# Lab2.net
KiCad netlist of a schematic drawn in Altium Designer
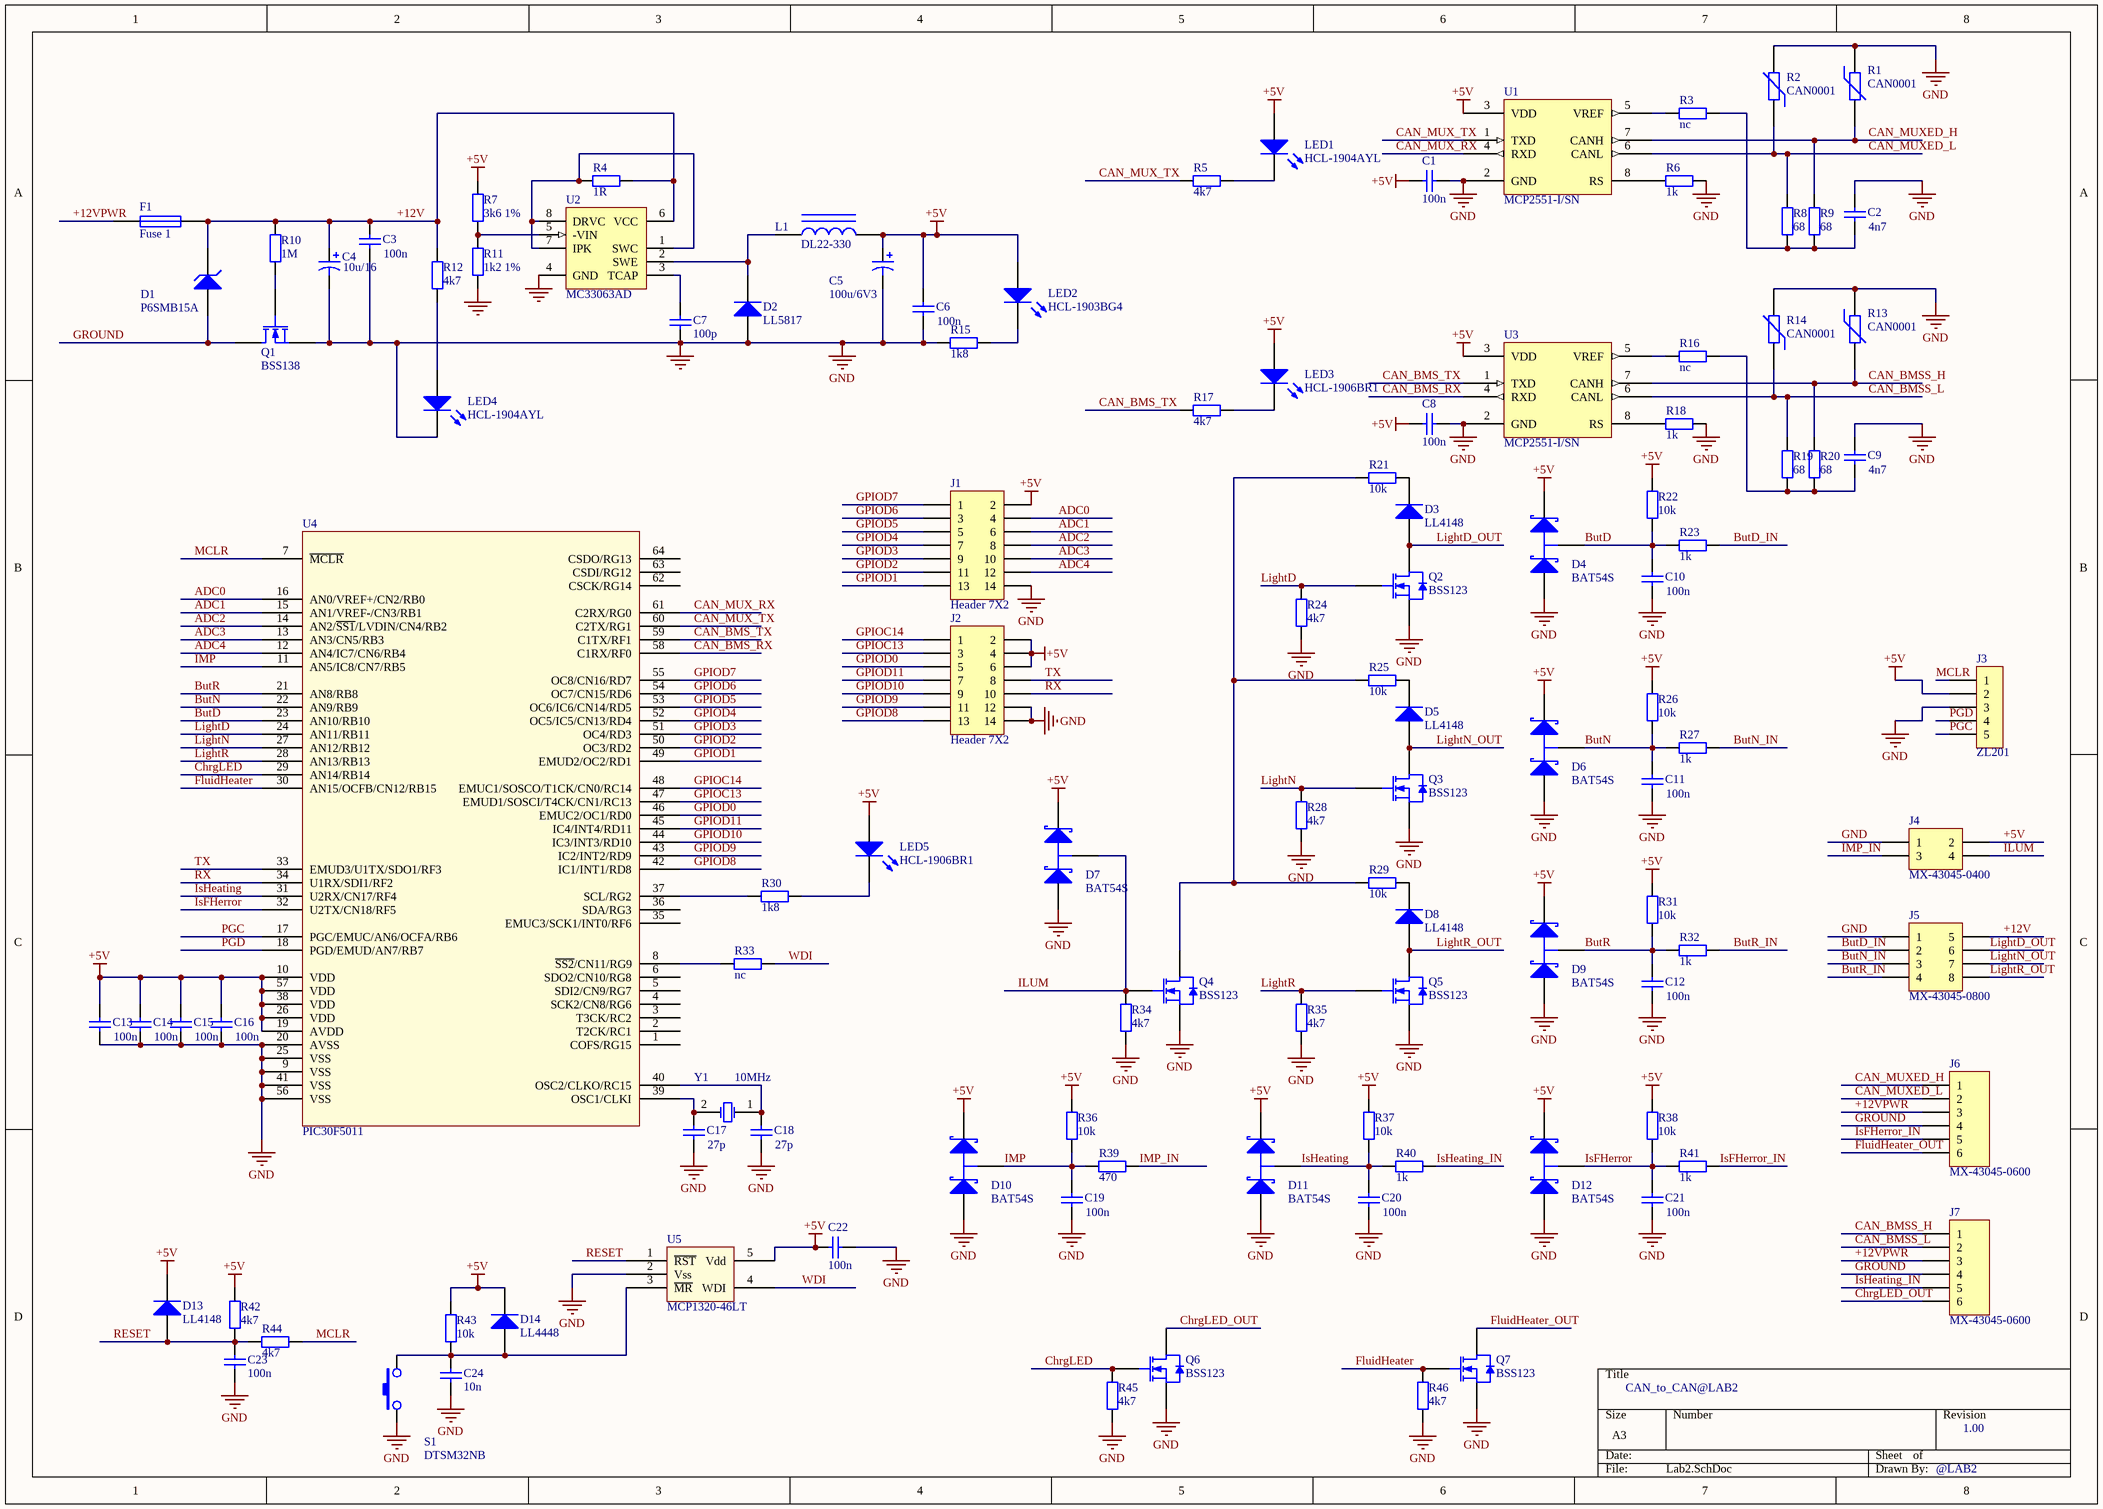
[diagram p0: Lab2.SchDoc]

(export (version "E")
  (design (tool "Eeschema 10.0.6"))
  (components
    (comp (ref "C1")
      (value "100n")
      (footprint "0603")
      (description "Capacitor")
      (libsource (lib "Miscellaneous Devices") (part "Cap"))
    )
    (comp (ref "C2")
      (value "4n7")
      (footprint "0603")
      (description "Capacitor")
      (libsource (lib "Miscellaneous Devices") (part "Cap"))
    )
    (comp (ref "C3")
      (value "100n")
      (footprint "3.5X2.8X1.9")
      (description "Capacitor")
      (libsource (lib "Miscellaneous Devices") (part "Cap"))
    )
    (comp (ref "C4")
      (value "10u/16")
      (footprint "3.5X2.8X1.9")
      (description "Polarized Capacitor (Radial)")
      (libsource (lib "Miscellaneous Devices") (part "Cap Pol1"))
    )
    (comp (ref "C5")
      (value "100u/6V3")
      (footprint "3.5X2.8X1.9")
      (description "Polarized Capacitor (Radial)")
      (libsource (lib "Miscellaneous Devices") (part "Cap Pol1"))
    )
    (comp (ref "C6")
      (value "100n")
      (footprint "0603")
      (description "Capacitor")
      (libsource (lib "Miscellaneous Devices") (part "Cap"))
    )
    (comp (ref "C7")
      (value "100p")
      (footprint "0603")
      (description "Capacitor")
      (libsource (lib "Miscellaneous Devices") (part "Cap"))
    )
    (comp (ref "C8")
      (value "100n")
      (footprint "0603")
      (description "Capacitor")
      (libsource (lib "Miscellaneous Devices") (part "Cap"))
    )
    (comp (ref "C9")
      (value "4n7")
      (footprint "0603")
      (description "Capacitor")
      (libsource (lib "Miscellaneous Devices") (part "Cap"))
    )
    (comp (ref "C10")
      (value "100n")
      (footprint "0603")
      (description "Capacitor")
      (libsource (lib "Miscellaneous Devices") (part "Cap"))
    )
    (comp (ref "C11")
      (value "100n")
      (footprint "0603")
      (description "Capacitor")
      (libsource (lib "Miscellaneous Devices") (part "Cap"))
    )
    (comp (ref "C12")
      (value "100n")
      (footprint "0603")
      (description "Capacitor")
      (libsource (lib "Miscellaneous Devices") (part "Cap"))
    )
    (comp (ref "C13")
      (value "100n")
      (footprint "0603")
      (description "Capacitor")
      (libsource (lib "Miscellaneous Devices") (part "Cap"))
    )
    (comp (ref "C14")
      (value "100n")
      (footprint "0603")
      (description "Capacitor")
      (libsource (lib "Miscellaneous Devices") (part "Cap"))
    )
    (comp (ref "C15")
      (value "100n")
      (footprint "0603")
      (description "Capacitor")
      (libsource (lib "Miscellaneous Devices") (part "Cap"))
    )
    (comp (ref "C16")
      (value "100n")
      (footprint "0603")
      (description "Capacitor")
      (libsource (lib "Miscellaneous Devices") (part "Cap"))
    )
    (comp (ref "C17")
      (value "27p")
      (footprint "0603")
      (description "Capacitor")
      (libsource (lib "Miscellaneous Devices") (part "Cap"))
    )
    (comp (ref "C18")
      (value "27p")
      (footprint "0603")
      (description "Capacitor")
      (libsource (lib "Miscellaneous Devices") (part "Cap"))
    )
    (comp (ref "C19")
      (value "100n")
      (footprint "0603")
      (description "Capacitor")
      (libsource (lib "Miscellaneous Devices") (part "Cap"))
    )
    (comp (ref "C20")
      (value "100n")
      (footprint "0603")
      (description "Capacitor")
      (libsource (lib "Miscellaneous Devices") (part "Cap"))
    )
    (comp (ref "C21")
      (value "100n")
      (footprint "0603")
      (description "Capacitor")
      (libsource (lib "Miscellaneous Devices") (part "Cap"))
    )
    (comp (ref "C22")
      (value "100n")
      (footprint "0603")
      (description "Capacitor")
      (libsource (lib "Miscellaneous Devices") (part "Cap"))
    )
    (comp (ref "C23")
      (value "100n")
      (footprint "0603")
      (description "Capacitor")
      (libsource (lib "Miscellaneous Devices") (part "Cap"))
    )
    (comp (ref "C24")
      (value "10n")
      (footprint "0603")
      (description "Capacitor")
      (libsource (lib "Miscellaneous Devices") (part "Cap"))
    )
    (comp (ref "D1")
      (value "P6SMB15A")
      (footprint "SMB")
      (description "Zener Diode")
      (libsource (lib "Miscellaneous Devices") (part "D Zener"))
    )
    (comp (ref "D2")
      (value "LL5817")
      (footprint "425")
      (description "High Conductance Fast Diode")
      (libsource (lib "FSC Discrete Diode") (part "1N4148"))
    )
    (comp (ref "D3")
      (value "LL4148")
      (footprint "6-0805_L")
      (description "High Conductance Fast Diode")
      (libsource (lib "FSC Discrete Diode") (part "1N4148"))
    )
    (comp (ref "D4")
      (value "BAT54S")
      (footprint "6-0805_L")
      (description "Schottky Barrier Double Diode")
      (libsource (lib "Philips Discrete Diode - Schottky") (part "BAT54S"))
    )
    (comp (ref "D5")
      (value "LL4148")
      (footprint "6-0805_L")
      (description "High Conductance Fast Diode")
      (libsource (lib "FSC Discrete Diode") (part "1N4148"))
    )
    (comp (ref "D6")
      (value "BAT54S")
      (footprint "SOT23_M")
      (description "Schottky Barrier Double Diode")
      (libsource (lib "Philips Discrete Diode - Schottky") (part "BAT54S"))
    )
    (comp (ref "D7")
      (value "BAT54S")
      (footprint "SOT-23B_M")
      (description "Schottky Barrier Double Diode")
      (libsource (lib "Philips Discrete Diode - Schottky") (part "BAT54S"))
    )
    (comp (ref "D8")
      (value "LL4148")
      (footprint "6-0805_L")
      (description "High Conductance Fast Diode")
      (libsource (lib "FSC Discrete Diode") (part "1N4148"))
    )
    (comp (ref "D9")
      (value "BAT54S")
      (footprint "SOT23_M")
      (description "Schottky Barrier Double Diode")
      (libsource (lib "Philips Discrete Diode - Schottky") (part "BAT54S"))
    )
    (comp (ref "D10")
      (value "BAT54S")
      (footprint "SOT23_M")
      (description "Schottky Barrier Double Diode")
      (libsource (lib "Philips Discrete Diode - Schottky") (part "BAT54S"))
    )
    (comp (ref "D11")
      (value "BAT54S")
      (footprint "SOT23_M")
      (description "Schottky Barrier Double Diode")
      (libsource (lib "Philips Discrete Diode - Schottky") (part "BAT54S"))
    )
    (comp (ref "D12")
      (value "BAT54S")
      (footprint "SOT23_M")
      (description "Schottky Barrier Double Diode")
      (libsource (lib "Philips Discrete Diode - Schottky") (part "BAT54S"))
    )
    (comp (ref "D13")
      (value "LL4148")
      (footprint "3.2X1.6X1.1")
      (description "High Conductance Fast Diode")
      (libsource (lib "FSC Discrete Diode") (part "1N4148"))
    )
    (comp (ref "D14")
      (value "LL4448")
      (footprint "3.2X1.6X1.1")
      (description "Default Diode")
      (libsource (lib "Miscellaneous Devices") (part "Diode"))
    )
    (comp (ref "F1")
      (value "Fuse 1")
      (footprint "1812")
      (description "Fuse")
      (libsource (lib "Miscellaneous Devices") (part "Fuse 1"))
    )
    (comp (ref "J1")
      (value "Header 7X2")
      (footprint "HDR2X7")
      (description "Header, 7-Pin, Dual row")
      (libsource (lib "Miscellaneous Connectors") (part "Header 7X2"))
    )
    (comp (ref "J2")
      (value "Header 7X2")
      (footprint "HDR2X7")
      (description "Header, 7-Pin, Dual row")
      (libsource (lib "Miscellaneous Connectors") (part "Header 7X2"))
    )
    (comp (ref "J3")
      (value "ZL201")
      (footprint "HDR1X5")
      (description "Connector")
      (libsource (lib "*") (part "CON5"))
    )
    (comp (ref "J4")
      (value "MX-43045-0400")
      (footprint "HDR2X2")
      (description "Header, 2-Pin, Dual row")
      (libsource (lib "Miscellaneous Connectors") (part "Header 2X2"))
    )
    (comp (ref "J5")
      (value "MX-43045-0800")
      (footprint "HDR2X4")
      (description "Header, 4-Pin, Dual row")
      (libsource (lib "Miscellaneous Connectors") (part "Header 4X2A"))
    )
    (comp (ref "J6")
      (value "MX-43045-0600")
      (footprint "HDR2X3")
      (description "Header, 6-Pin")
      (libsource (lib "Miscellaneous Connectors") (part "Header 6"))
    )
    (comp (ref "J7")
      (value "MX-43045-0600")
      (footprint "HDR2X3")
      (description "Header, 6-Pin")
      (libsource (lib "Miscellaneous Connectors") (part "Header 6"))
    )
    (comp (ref "L1")
      (value "DL22-330")
      (footprint "AXIAL-0.4")
      (description "Magnetic-Core Inductor")
      (libsource (lib "Miscellaneous Devices") (part "Inductor Iron"))
    )
    (comp (ref "LED1")
      (value "HCL-1904AYL")
      (footprint "0603")
      (description "Typical BLUE SiC LED")
      (libsource (lib "Miscellaneous Devices") (part "LED3"))
    )
    (comp (ref "LED2")
      (value "HCL-1903BG4")
      (footprint "0603")
      (description "Typical BLUE SiC LED")
      (libsource (lib "Miscellaneous Devices") (part "LED3"))
    )
    (comp (ref "LED3")
      (value "HCL-1906BR1")
      (footprint "0603")
      (description "Typical BLUE SiC LED")
      (libsource (lib "Miscellaneous Devices") (part "LED3"))
    )
    (comp (ref "LED4")
      (value "HCL-1904AYL")
      (footprint "0603")
      (description "Typical BLUE SiC LED")
      (libsource (lib "Miscellaneous Devices") (part "LED3"))
    )
    (comp (ref "LED5")
      (value "HCL-1906BR1")
      (footprint "0603")
      (description "Typical BLUE SiC LED")
      (libsource (lib "Miscellaneous Devices") (part "LED3"))
    )
    (comp (ref "Q1")
      (value "BSS138")
      (footprint "SOT-23_L")
      (description "N-Channel Enhancement Mode Vertical DMOS FET")
      (libsource (lib "Zetex Discrete MOSFET") (part "BSS138"))
    )
    (comp (ref "Q2")
      (value "BSS123")
      (footprint "SOT23_M")
      (description "N-channel Enhancement Mode Vertical D-MOSFET")
      (libsource (lib "Philips Discrete MOSFET - Low Power") (part "BSS123"))
    )
    (comp (ref "Q3")
      (value "BSS123")
      (footprint "SOT-23_L")
      (description "N-channel Enhancement Mode Vertical D-MOSFET")
      (libsource (lib "Philips Discrete MOSFET - Low Power") (part "BSS123"))
    )
    (comp (ref "Q4")
      (value "BSS123")
      (footprint "SOT23_M")
      (description "N-channel Enhancement Mode Vertical D-MOSFET")
      (libsource (lib "Philips Discrete MOSFET - Low Power") (part "BSS123"))
    )
    (comp (ref "Q5")
      (value "BSS123")
      (footprint "SOT23_L")
      (description "N-channel Enhancement Mode Vertical D-MOSFET")
      (libsource (lib "Philips Discrete MOSFET - Low Power") (part "BSS123"))
    )
    (comp (ref "Q6")
      (value "BSS123")
      (footprint "SOT-23_M")
      (description "N-channel Enhancement Mode Vertical D-MOSFET")
      (libsource (lib "Philips Discrete MOSFET - Low Power") (part "BSS123"))
    )
    (comp (ref "Q7")
      (value "BSS123")
      (footprint "SOT23_M")
      (description "N-channel Enhancement Mode Vertical D-MOSFET")
      (libsource (lib "Philips Discrete MOSFET - Low Power") (part "BSS123"))
    )
    (comp (ref "R1")
      (value "CAN0001")
      (footprint "0603")
      (description "Varistor (Voltage-Sensitive Resistor)")
      (libsource (lib "Miscellaneous Devices") (part "Res Varistor"))
    )
    (comp (ref "R2")
      (value "CAN0001")
      (footprint "0603")
      (description "Varistor (Voltage-Sensitive Resistor)")
      (libsource (lib "Miscellaneous Devices") (part "Res Varistor"))
    )
    (comp (ref "R3")
      (value "nc")
      (footprint "0603")
      (description "Resistor")
      (libsource (lib "Miscellaneous Devices") (part "Res2"))
    )
    (comp (ref "R4")
      (value "1R")
      (footprint "0603")
      (description "Resistor")
      (libsource (lib "Miscellaneous Devices") (part "Res2"))
    )
    (comp (ref "R5")
      (value "4k7")
      (footprint "0603")
      (description "Resistor")
      (libsource (lib "") (part "Res2_2"))
    )
    (comp (ref "R6")
      (value "1k")
      (footprint "0603")
      (description "Resistor")
      (libsource (lib "Miscellaneous Devices") (part "Res2"))
    )
    (comp (ref "R7")
      (value "3k6 1%")
      (footprint "0603")
      (description "Resistor")
      (libsource (lib "") (part "Res2_1"))
    )
    (comp (ref "R8")
      (value "68")
      (footprint "0603")
      (description "Resistor")
      (libsource (lib "") (part "Res2_1"))
    )
    (comp (ref "R9")
      (value "68")
      (footprint "0603")
      (description "Resistor")
      (libsource (lib "") (part "Res2_1"))
    )
    (comp (ref "R10")
      (value "1M")
      (footprint "0603")
      (description "Resistor")
      (libsource (lib "") (part "Res2_1"))
    )
    (comp (ref "R11")
      (value "1k2 1%")
      (footprint "0603")
      (description "Resistor")
      (libsource (lib "") (part "Res2_3"))
    )
    (comp (ref "R12")
      (value "4k7")
      (footprint "0603")
      (description "Resistor")
      (libsource (lib "") (part "Res2_1"))
    )
    (comp (ref "R13")
      (value "CAN0001")
      (footprint "0603")
      (description "Varistor (Voltage-Sensitive Resistor)")
      (libsource (lib "Miscellaneous Devices") (part "Res Varistor"))
    )
    (comp (ref "R14")
      (value "CAN0001")
      (footprint "0603")
      (description "Varistor (Voltage-Sensitive Resistor)")
      (libsource (lib "Miscellaneous Devices") (part "Res Varistor"))
    )
    (comp (ref "R15")
      (value "1k8")
      (footprint "0603")
      (description "Resistor")
      (libsource (lib "") (part "Res2_2"))
    )
    (comp (ref "R16")
      (value "nc")
      (footprint "0603")
      (description "Resistor")
      (libsource (lib "Miscellaneous Devices") (part "Res2"))
    )
    (comp (ref "R17")
      (value "4k7")
      (footprint "0603")
      (description "Resistor")
      (libsource (lib "") (part "Res2_2"))
    )
    (comp (ref "R18")
      (value "1k")
      (footprint "0603")
      (description "Resistor")
      (libsource (lib "Miscellaneous Devices") (part "Res2"))
    )
    (comp (ref "R19")
      (value "68")
      (footprint "0603")
      (description "Resistor")
      (libsource (lib "") (part "Res2_1"))
    )
    (comp (ref "R20")
      (value "68")
      (footprint "0603")
      (description "Resistor")
      (libsource (lib "") (part "Res2_1"))
    )
    (comp (ref "R21")
      (value "10k")
      (footprint "0603")
      (description "Resistor")
      (libsource (lib "Miscellaneous Devices") (part "Res2"))
    )
    (comp (ref "R22")
      (value "10k")
      (footprint "0603")
      (description "Resistor")
      (libsource (lib "") (part "Res2_1"))
    )
    (comp (ref "R23")
      (value "1k")
      (footprint "0603")
      (description "Resistor")
      (libsource (lib "") (part "Res2_2"))
    )
    (comp (ref "R24")
      (value "4k7")
      (footprint "0603")
      (description "Resistor")
      (libsource (lib "") (part "Res2_1"))
    )
    (comp (ref "R25")
      (value "10k")
      (footprint "0603")
      (description "Resistor")
      (libsource (lib "Miscellaneous Devices") (part "Res2"))
    )
    (comp (ref "R26")
      (value "10k")
      (footprint "0603")
      (description "Resistor")
      (libsource (lib "") (part "Res2_1"))
    )
    (comp (ref "R27")
      (value "1k")
      (footprint "0603")
      (description "Resistor")
      (libsource (lib "") (part "Res2_2"))
    )
    (comp (ref "R28")
      (value "4k7")
      (footprint "0603")
      (description "Resistor")
      (libsource (lib "") (part "Res2_1"))
    )
    (comp (ref "R29")
      (value "10k")
      (footprint "0603")
      (description "Resistor")
      (libsource (lib "Miscellaneous Devices") (part "Res2"))
    )
    (comp (ref "R30")
      (value "1k8")
      (footprint "0603")
      (description "Resistor")
      (libsource (lib "") (part "Res2_2"))
    )
    (comp (ref "R31")
      (value "10k")
      (footprint "0603")
      (description "Resistor")
      (libsource (lib "") (part "Res2_1"))
    )
    (comp (ref "R32")
      (value "1k")
      (footprint "0603")
      (description "Resistor")
      (libsource (lib "") (part "Res2_2"))
    )
    (comp (ref "R33")
      (value "nc")
      (footprint "0603")
      (description "Resistor")
      (libsource (lib "") (part "Res2_2"))
    )
    (comp (ref "R34")
      (value "4k7")
      (footprint "0603")
      (description "Resistor")
      (libsource (lib "") (part "Res2_1"))
    )
    (comp (ref "R35")
      (value "4k7")
      (footprint "0603")
      (description "Resistor")
      (libsource (lib "") (part "Res2_1"))
    )
    (comp (ref "R36")
      (value "10k")
      (footprint "0603")
      (description "Resistor")
      (libsource (lib "") (part "Res2_1"))
    )
    (comp (ref "R37")
      (value "10k")
      (footprint "0603")
      (description "Resistor")
      (libsource (lib "") (part "Res2_1"))
    )
    (comp (ref "R38")
      (value "10k")
      (footprint "0603")
      (description "Resistor")
      (libsource (lib "") (part "Res2_1"))
    )
    (comp (ref "R39")
      (value "470")
      (footprint "0603")
      (description "Resistor")
      (libsource (lib "") (part "Res2_2"))
    )
    (comp (ref "R40")
      (value "1k")
      (footprint "0603")
      (description "Resistor")
      (libsource (lib "") (part "Res2_2"))
    )
    (comp (ref "R41")
      (value "1k")
      (footprint "0603")
      (description "Resistor")
      (libsource (lib "") (part "Res2_2"))
    )
    (comp (ref "R42")
      (value "4k7")
      (footprint "0603")
      (description "Resistor")
      (libsource (lib "") (part "Res2_1"))
    )
    (comp (ref "R43")
      (value "10k")
      (footprint "0603")
      (description "Resistor")
      (libsource (lib "") (part "Res2_3"))
    )
    (comp (ref "R44")
      (value "4k7")
      (footprint "0603")
      (description "Resistor")
      (libsource (lib "") (part "Res2_2"))
    )
    (comp (ref "R45")
      (value "4k7")
      (footprint "0603")
      (description "Resistor")
      (libsource (lib "") (part "Res2_1"))
    )
    (comp (ref "R46")
      (value "4k7")
      (footprint "0603")
      (description "Resistor")
      (libsource (lib "") (part "Res2_1"))
    )
    (comp (ref "S1")
      (value "DTSM32NB")
      (footprint "0603")
      (description "Switch PushButton")
      (libsource (lib "*") (part "PUSHB"))
    )
    (comp (ref "U1")
      (value "MCP2551-I/SN")
      (footprint "SO8_L")
      (description "High Speed CAN Transceiver, 8-Pin Plastic SOIC, Industrial Grade")
      (libsource (lib "Microchip Interface Line Transceiver") (part "MCP2551-I/SN"))
    )
    (comp (ref "U2")
      (value "MC33063AD")
      (footprint "SO8_N")
      (description "DC-to-DC Converter Control Circuit")
      (libsource (lib "Motorola Power Mgt DC-DC Converter") (part "MC33063AD"))
    )
    (comp (ref "U3")
      (value "MCP2551-I/SN")
      (footprint "SO8_L")
      (description "High Speed CAN Transceiver, 8-Pin Plastic SOIC, Industrial Grade")
      (libsource (lib "Microchip Interface Line Transceiver") (part "MCP2551-I/SN"))
    )
    (comp (ref "U4")
      (value "PIC30F5011")
      (footprint "CP-64-1_N")
      (description "PIC30F5011 - Up")
      (libsource (lib "X-Tro's Misc") (part "PIC30F5011"))
    )
    (comp (ref "U5")
      (value "MCP1320-46LT")
      (footprint "SOT23-6_M")
      (libsource (lib "X-Tro's Misc") (part "MCP1320"))
    )
    (comp (ref "Y1")
      (value "10MHz")
      (footprint "0402")
      (description "Crystal Oscillator")
      (libsource (lib "Miscellaneous Devices") (part "XTAL"))
    )
  )
  (nets
    (net (code "1") (name "+5V") (class "Default")
      (node (ref "C1") (pin "1") (pinfunction "1_1") (pintype "passive"))
      (node (ref "C13") (pin "1") (pinfunction "1_1") (pintype "passive"))
      (node (ref "C14") (pin "1") (pinfunction "1_1") (pintype "passive"))
      (node (ref "C15") (pin "1") (pinfunction "1_1") (pintype "passive"))
      (node (ref "C16") (pin "1") (pinfunction "1_1") (pintype "passive"))
      (node (ref "C22") (pin "1") (pinfunction "1_1") (pintype "passive"))
      (node (ref "C5") (pin "1") (pinfunction "1_1") (pintype "passive"))
      (node (ref "C6") (pin "1") (pinfunction "1_1") (pintype "passive"))
      (node (ref "C8") (pin "1") (pinfunction "1_1") (pintype "passive"))
      (node (ref "D10") (pin "2") (pinfunction "K_2") (pintype "passive"))
      (node (ref "D11") (pin "2") (pinfunction "K_2") (pintype "passive"))
      (node (ref "D12") (pin "2") (pinfunction "K_2") (pintype "passive"))
      (node (ref "D13") (pin "2") (pinfunction "K_2") (pintype "passive"))
      (node (ref "D14") (pin "2") (pinfunction "K_2") (pintype "passive"))
      (node (ref "D4") (pin "2") (pinfunction "K_2") (pintype "passive"))
      (node (ref "D6") (pin "2") (pinfunction "K_2") (pintype "passive"))
      (node (ref "D7") (pin "2") (pinfunction "K_2") (pintype "passive"))
      (node (ref "D9") (pin "2") (pinfunction "K_2") (pintype "passive"))
      (node (ref "J1") (pin "2") (pinfunction "2_2") (pintype "passive"))
      (node (ref "J2") (pin "2") (pinfunction "2_2") (pintype "passive"))
      (node (ref "J2") (pin "4") (pinfunction "4_4") (pintype "passive"))
      (node (ref "J2") (pin "6") (pinfunction "6_6") (pintype "passive"))
      (node (ref "J3") (pin "2") (pinfunction "2_2") (pintype "passive"))
      (node (ref "J4") (pin "2") (pinfunction "2_2") (pintype "passive"))
      (node (ref "L1") (pin "2") (pinfunction "2_2") (pintype "passive"))
      (node (ref "LED1") (pin "1") (pinfunction "A_1") (pintype "passive"))
      (node (ref "LED2") (pin "1") (pinfunction "A_1") (pintype "passive"))
      (node (ref "LED3") (pin "1") (pinfunction "A_1") (pintype "passive"))
      (node (ref "LED5") (pin "1") (pinfunction "A_1") (pintype "passive"))
      (node (ref "R22") (pin "1") (pinfunction "1_1") (pintype "passive"))
      (node (ref "R26") (pin "1") (pinfunction "1_1") (pintype "passive"))
      (node (ref "R31") (pin "1") (pinfunction "1_1") (pintype "passive"))
      (node (ref "R36") (pin "1") (pinfunction "1_1") (pintype "passive"))
      (node (ref "R37") (pin "1") (pinfunction "1_1") (pintype "passive"))
      (node (ref "R38") (pin "1") (pinfunction "1_1") (pintype "passive"))
      (node (ref "R42") (pin "1") (pinfunction "1_1") (pintype "passive"))
      (node (ref "R43") (pin "2") (pinfunction "2_2") (pintype "passive"))
      (node (ref "R7") (pin "1") (pinfunction "1_1") (pintype "passive"))
      (node (ref "U1") (pin "3") (pinfunction "VDD_3") (pintype "power_in"))
      (node (ref "U3") (pin "3") (pinfunction "VDD_3") (pintype "power_in"))
      (node (ref "U4") (pin "10") (pinfunction "VDD_10") (pintype "passive"))
      (node (ref "U4") (pin "19") (pinfunction "AVDD_19") (pintype "passive"))
      (node (ref "U4") (pin "26") (pinfunction "VDD_26") (pintype "passive"))
      (node (ref "U4") (pin "38") (pinfunction "VDD_38") (pintype "passive"))
      (node (ref "U4") (pin "57") (pinfunction "VDD_57") (pintype "passive"))
      (node (ref "U5") (pin "5") (pinfunction "Vdd_5") (pintype "passive"))
    )
    (net (code "2") (name "/+12V") (class "Default")
      (node (ref "C3") (pin "1") (pinfunction "1_1") (pintype "passive"))
      (node (ref "C4") (pin "1") (pinfunction "1_1") (pintype "passive"))
      (node (ref "D1") (pin "2") (pinfunction "K_2") (pintype "passive"))
      (node (ref "F1") (pin "2") (pinfunction "2_2") (pintype "passive"))
      (node (ref "J5") (pin "5") (pinfunction "5_5") (pintype "passive"))
      (node (ref "R10") (pin "1") (pinfunction "1_1") (pintype "passive"))
      (node (ref "R12") (pin "1") (pinfunction "1_1") (pintype "passive"))
      (node (ref "R4") (pin "2") (pinfunction "2_2") (pintype "passive"))
      (node (ref "U2") (pin "6") (pinfunction "VCC_6") (pintype "power_in"))
    )
    (net (code "3") (name "/+12VPWR") (class "Default")
      (node (ref "F1") (pin "1") (pinfunction "1_1") (pintype "passive"))
      (node (ref "J6") (pin "3") (pinfunction "3_3") (pintype "passive"))
      (node (ref "J7") (pin "3") (pinfunction "3_3") (pintype "passive"))
    )
    (net (code "4") (name "/ADC0") (class "Default")
      (node (ref "J1") (pin "4") (pinfunction "4_4") (pintype "passive"))
      (node (ref "U4") (pin "16") (pinfunction "AN0/VREF+/CN2/RB0_16") (pintype "passive"))
    )
    (net (code "5") (name "/ADC1") (class "Default")
      (node (ref "J1") (pin "6") (pinfunction "6_6") (pintype "passive"))
      (node (ref "U4") (pin "15") (pinfunction "AN1/VREF-/CN3/RB1_15") (pintype "passive"))
    )
    (net (code "6") (name "/ADC2") (class "Default")
      (node (ref "J1") (pin "8") (pinfunction "8_8") (pintype "passive"))
      (node (ref "U4") (pin "14") (pinfunction "AN2/~{SS1}/LVDIN/CN4/RB2_14") (pintype "passive"))
    )
    (net (code "7") (name "/ADC3") (class "Default")
      (node (ref "J1") (pin "10") (pinfunction "10_10") (pintype "passive"))
      (node (ref "U4") (pin "13") (pinfunction "AN3/CN5/RB3_13") (pintype "passive"))
    )
    (net (code "8") (name "/ADC4") (class "Default")
      (node (ref "J1") (pin "12") (pinfunction "12_12") (pintype "passive"))
      (node (ref "U4") (pin "12") (pinfunction "AN4/IC7/CN6/RB4_12") (pintype "passive"))
    )
    (net (code "9") (name "/ButD") (class "Default")
      (node (ref "C10") (pin "1") (pinfunction "1_1") (pintype "passive"))
      (node (ref "D4") (pin "3") (pinfunction "C_3") (pintype "passive"))
      (node (ref "R22") (pin "2") (pinfunction "2_2") (pintype "passive"))
      (node (ref "R23") (pin "2") (pinfunction "2_2") (pintype "passive"))
      (node (ref "U4") (pin "23") (pinfunction "AN10/RB10_23") (pintype "passive"))
    )
    (net (code "10") (name "/ButD_IN") (class "Default")
      (node (ref "J5") (pin "2") (pinfunction "2_2") (pintype "passive"))
      (node (ref "R23") (pin "1") (pinfunction "1_1") (pintype "passive"))
    )
    (net (code "11") (name "/ButN") (class "Default")
      (node (ref "C11") (pin "1") (pinfunction "1_1") (pintype "passive"))
      (node (ref "D6") (pin "3") (pinfunction "C_3") (pintype "passive"))
      (node (ref "R26") (pin "2") (pinfunction "2_2") (pintype "passive"))
      (node (ref "R27") (pin "2") (pinfunction "2_2") (pintype "passive"))
      (node (ref "U4") (pin "22") (pinfunction "AN9/RB9_22") (pintype "passive"))
    )
    (net (code "12") (name "/ButN_IN") (class "Default")
      (node (ref "J5") (pin "3") (pinfunction "3_3") (pintype "passive"))
      (node (ref "R27") (pin "1") (pinfunction "1_1") (pintype "passive"))
    )
    (net (code "13") (name "/ButR") (class "Default")
      (node (ref "C12") (pin "1") (pinfunction "1_1") (pintype "passive"))
      (node (ref "D9") (pin "3") (pinfunction "C_3") (pintype "passive"))
      (node (ref "R31") (pin "2") (pinfunction "2_2") (pintype "passive"))
      (node (ref "R32") (pin "2") (pinfunction "2_2") (pintype "passive"))
      (node (ref "U4") (pin "21") (pinfunction "AN8/RB8_21") (pintype "passive"))
    )
    (net (code "14") (name "/ButR_IN") (class "Default")
      (node (ref "J5") (pin "4") (pinfunction "4_4") (pintype "passive"))
      (node (ref "R32") (pin "1") (pinfunction "1_1") (pintype "passive"))
    )
    (net (code "15") (name "/CAN_BMSS_H") (class "Default")
      (node (ref "J7") (pin "1") (pinfunction "1_1") (pintype "passive"))
      (node (ref "R13") (pin "2") (pinfunction "2_2") (pintype "passive"))
      (node (ref "R20") (pin "1") (pinfunction "1_1") (pintype "passive"))
      (node (ref "U3") (pin "7") (pinfunction "CANH_7") (pintype "output"))
    )
    (net (code "16") (name "/CAN_BMSS_L") (class "Default")
      (node (ref "J7") (pin "2") (pinfunction "2_2") (pintype "passive"))
      (node (ref "R14") (pin "1") (pinfunction "1_1") (pintype "passive"))
      (node (ref "R19") (pin "1") (pinfunction "1_1") (pintype "passive"))
      (node (ref "U3") (pin "6") (pinfunction "CANL_6") (pintype "output"))
    )
    (net (code "17") (name "/CAN_BMS_RX") (class "Default")
      (node (ref "U3") (pin "4") (pinfunction "RXD_4") (pintype "output"))
      (node (ref "U4") (pin "58") (pinfunction "C1RX/RF0_58") (pintype "passive"))
    )
    (net (code "18") (name "/CAN_BMS_TX") (class "Default")
      (node (ref "R17") (pin "2") (pinfunction "2_2") (pintype "passive"))
      (node (ref "U3") (pin "1") (pinfunction "TXD_1") (pintype "input"))
      (node (ref "U4") (pin "59") (pinfunction "C1TX/RF1_59") (pintype "passive"))
    )
    (net (code "19") (name "/CAN_MUXED_H") (class "Default")
      (node (ref "J6") (pin "1") (pinfunction "1_1") (pintype "passive"))
      (node (ref "R1") (pin "2") (pinfunction "2_2") (pintype "passive"))
      (node (ref "R9") (pin "1") (pinfunction "1_1") (pintype "passive"))
      (node (ref "U1") (pin "7") (pinfunction "CANH_7") (pintype "output"))
    )
    (net (code "20") (name "/CAN_MUXED_L") (class "Default")
      (node (ref "J6") (pin "2") (pinfunction "2_2") (pintype "passive"))
      (node (ref "R2") (pin "1") (pinfunction "1_1") (pintype "passive"))
      (node (ref "R8") (pin "1") (pinfunction "1_1") (pintype "passive"))
      (node (ref "U1") (pin "6") (pinfunction "CANL_6") (pintype "output"))
    )
    (net (code "21") (name "/CAN_MUX_RX") (class "Default")
      (node (ref "U1") (pin "4") (pinfunction "RXD_4") (pintype "output"))
      (node (ref "U4") (pin "61") (pinfunction "C2RX/RG0_61") (pintype "passive"))
    )
    (net (code "22") (name "/CAN_MUX_TX") (class "Default")
      (node (ref "R5") (pin "2") (pinfunction "2_2") (pintype "passive"))
      (node (ref "U1") (pin "1") (pinfunction "TXD_1") (pintype "input"))
      (node (ref "U4") (pin "60") (pinfunction "C2TX/RG1_60") (pintype "passive"))
    )
    (net (code "23") (name "/ChrgLED") (class "Default")
      (node (ref "Q6") (pin "3") (pinfunction "G_3") (pintype "passive"))
      (node (ref "R45") (pin "1") (pinfunction "1_1") (pintype "passive"))
      (node (ref "U4") (pin "29") (pinfunction "AN14/RB14_29") (pintype "passive"))
    )
    (net (code "24") (name "/ChrgLED_OUT") (class "Default")
      (node (ref "J7") (pin "6") (pinfunction "6_6") (pintype "passive"))
      (node (ref "Q6") (pin "1") (pinfunction "D_1") (pintype "passive"))
    )
    (net (code "25") (name "/FluidHeater") (class "Default")
      (node (ref "Q7") (pin "3") (pinfunction "G_3") (pintype "passive"))
      (node (ref "R46") (pin "1") (pinfunction "1_1") (pintype "passive"))
      (node (ref "U4") (pin "30") (pinfunction "AN15/OCFB/CN12/RB15_30") (pintype "passive"))
    )
    (net (code "26") (name "/FluidHeater_OUT") (class "Default")
      (node (ref "J6") (pin "6") (pinfunction "6_6") (pintype "passive"))
      (node (ref "Q7") (pin "1") (pinfunction "D_1") (pintype "passive"))
    )
    (net (code "27") (name "/GPIOC13") (class "Default")
      (node (ref "J2") (pin "3") (pinfunction "3_3") (pintype "passive"))
      (node (ref "U4") (pin "47") (pinfunction "EMUD1/SOSCI/T4CK/CN1/RC13_47") (pintype "passive"))
    )
    (net (code "28") (name "/GPIOC14") (class "Default")
      (node (ref "J2") (pin "1") (pinfunction "1_1") (pintype "passive"))
      (node (ref "U4") (pin "48") (pinfunction "EMUC1/SOSCO/T1CK/CN0/RC14_48") (pintype "passive"))
    )
    (net (code "29") (name "/GPIOD0") (class "Default")
      (node (ref "J2") (pin "5") (pinfunction "5_5") (pintype "passive"))
      (node (ref "U4") (pin "46") (pinfunction "EMUC2/OC1/RD0_46") (pintype "passive"))
    )
    (net (code "30") (name "/GPIOD1") (class "Default")
      (node (ref "J1") (pin "13") (pinfunction "13_13") (pintype "passive"))
      (node (ref "U4") (pin "49") (pinfunction "EMUD2/OC2/RD1_49") (pintype "passive"))
    )
    (net (code "31") (name "/GPIOD2") (class "Default")
      (node (ref "J1") (pin "11") (pinfunction "11_11") (pintype "passive"))
      (node (ref "U4") (pin "50") (pinfunction "OC3/RD2_50") (pintype "passive"))
    )
    (net (code "32") (name "/GPIOD3") (class "Default")
      (node (ref "J1") (pin "9") (pinfunction "9_9") (pintype "passive"))
      (node (ref "U4") (pin "51") (pinfunction "OC4/RD3_51") (pintype "passive"))
    )
    (net (code "33") (name "/GPIOD4") (class "Default")
      (node (ref "J1") (pin "7") (pinfunction "7_7") (pintype "passive"))
      (node (ref "U4") (pin "52") (pinfunction "OC5/IC5/CN13/RD4_52") (pintype "passive"))
    )
    (net (code "34") (name "/GPIOD5") (class "Default")
      (node (ref "J1") (pin "5") (pinfunction "5_5") (pintype "passive"))
      (node (ref "U4") (pin "53") (pinfunction "OC6/IC6/CN14/RD5_53") (pintype "passive"))
    )
    (net (code "35") (name "/GPIOD6") (class "Default")
      (node (ref "J1") (pin "3") (pinfunction "3_3") (pintype "passive"))
      (node (ref "U4") (pin "54") (pinfunction "OC7/CN15/RD6_54") (pintype "passive"))
    )
    (net (code "36") (name "/GPIOD7") (class "Default")
      (node (ref "J1") (pin "1") (pinfunction "1_1") (pintype "passive"))
      (node (ref "U4") (pin "55") (pinfunction "OC8/CN16/RD7_55") (pintype "passive"))
    )
    (net (code "37") (name "/GPIOD8") (class "Default")
      (node (ref "J2") (pin "13") (pinfunction "13_13") (pintype "passive"))
      (node (ref "U4") (pin "42") (pinfunction "IC1/INT1/RD8_42") (pintype "passive"))
    )
    (net (code "38") (name "/GPIOD9") (class "Default")
      (node (ref "J2") (pin "11") (pinfunction "11_11") (pintype "passive"))
      (node (ref "U4") (pin "43") (pinfunction "IC2/INT2/RD9_43") (pintype "passive"))
    )
    (net (code "39") (name "/GPIOD10") (class "Default")
      (node (ref "J2") (pin "9") (pinfunction "9_9") (pintype "passive"))
      (node (ref "U4") (pin "44") (pinfunction "IC3/INT3/RD10_44") (pintype "passive"))
    )
    (net (code "40") (name "/GPIOD11") (class "Default")
      (node (ref "J2") (pin "7") (pinfunction "7_7") (pintype "passive"))
      (node (ref "U4") (pin "45") (pinfunction "IC4/INT4/RD11_45") (pintype "passive"))
    )
    (net (code "41") (name "/GROUND") (class "Default")
      (node (ref "D1") (pin "1") (pinfunction "A_1") (pintype "passive"))
      (node (ref "J6") (pin "4") (pinfunction "4_4") (pintype "passive"))
      (node (ref "J7") (pin "4") (pinfunction "4_4") (pintype "passive"))
      (node (ref "Q1") (pin "1") (pinfunction "D_1") (pintype "passive"))
    )
    (net (code "42") (name "/ILUM") (class "Default")
      (node (ref "D7") (pin "3") (pinfunction "C_3") (pintype "passive"))
      (node (ref "J4") (pin "4") (pinfunction "4_4") (pintype "passive"))
      (node (ref "Q4") (pin "3") (pinfunction "G_3") (pintype "passive"))
      (node (ref "R34") (pin "1") (pinfunction "1_1") (pintype "passive"))
    )
    (net (code "43") (name "/IMP") (class "Default")
      (node (ref "C19") (pin "1") (pinfunction "1_1") (pintype "passive"))
      (node (ref "D10") (pin "3") (pinfunction "C_3") (pintype "passive"))
      (node (ref "R36") (pin "2") (pinfunction "2_2") (pintype "passive"))
      (node (ref "R39") (pin "2") (pinfunction "2_2") (pintype "passive"))
      (node (ref "U4") (pin "11") (pinfunction "AN5/IC8/CN7/RB5_11") (pintype "passive"))
    )
    (net (code "44") (name "/IMP_IN") (class "Default")
      (node (ref "J4") (pin "3") (pinfunction "3_3") (pintype "passive"))
      (node (ref "R39") (pin "1") (pinfunction "1_1") (pintype "passive"))
    )
    (net (code "45") (name "/IsFHerror") (class "Default")
      (node (ref "C21") (pin "1") (pinfunction "1_1") (pintype "passive"))
      (node (ref "D12") (pin "3") (pinfunction "C_3") (pintype "passive"))
      (node (ref "R38") (pin "2") (pinfunction "2_2") (pintype "passive"))
      (node (ref "R41") (pin "2") (pinfunction "2_2") (pintype "passive"))
      (node (ref "U4") (pin "32") (pinfunction "U2TX/CN18/RF5_32") (pintype "passive"))
    )
    (net (code "46") (name "/IsFHerror_IN") (class "Default")
      (node (ref "J6") (pin "5") (pinfunction "5_5") (pintype "passive"))
      (node (ref "R41") (pin "1") (pinfunction "1_1") (pintype "passive"))
    )
    (net (code "47") (name "/IsHeating") (class "Default")
      (node (ref "C20") (pin "1") (pinfunction "1_1") (pintype "passive"))
      (node (ref "D11") (pin "3") (pinfunction "C_3") (pintype "passive"))
      (node (ref "R37") (pin "2") (pinfunction "2_2") (pintype "passive"))
      (node (ref "R40") (pin "2") (pinfunction "2_2") (pintype "passive"))
      (node (ref "U4") (pin "31") (pinfunction "U2RX/CN17/RF4_31") (pintype "passive"))
    )
    (net (code "48") (name "/IsHeating_IN") (class "Default")
      (node (ref "J7") (pin "5") (pinfunction "5_5") (pintype "passive"))
      (node (ref "R40") (pin "1") (pinfunction "1_1") (pintype "passive"))
    )
    (net (code "49") (name "/LightD") (class "Default")
      (node (ref "Q2") (pin "3") (pinfunction "G_3") (pintype "passive"))
      (node (ref "R24") (pin "1") (pinfunction "1_1") (pintype "passive"))
      (node (ref "U4") (pin "24") (pinfunction "AN11/RB11_24") (pintype "passive"))
    )
    (net (code "50") (name "/LightD_OUT") (class "Default")
      (node (ref "D3") (pin "1") (pinfunction "A_1") (pintype "passive"))
      (node (ref "J5") (pin "6") (pinfunction "6_6") (pintype "passive"))
      (node (ref "Q2") (pin "1") (pinfunction "D_1") (pintype "passive"))
    )
    (net (code "51") (name "/LightN") (class "Default")
      (node (ref "Q3") (pin "3") (pinfunction "G_3") (pintype "passive"))
      (node (ref "R28") (pin "1") (pinfunction "1_1") (pintype "passive"))
      (node (ref "U4") (pin "27") (pinfunction "AN12/RB12_27") (pintype "passive"))
    )
    (net (code "52") (name "/LightN_OUT") (class "Default")
      (node (ref "D5") (pin "1") (pinfunction "A_1") (pintype "passive"))
      (node (ref "J5") (pin "7") (pinfunction "7_7") (pintype "passive"))
      (node (ref "Q3") (pin "1") (pinfunction "D_1") (pintype "passive"))
    )
    (net (code "53") (name "/LightR") (class "Default")
      (node (ref "Q5") (pin "3") (pinfunction "G_3") (pintype "passive"))
      (node (ref "R35") (pin "1") (pinfunction "1_1") (pintype "passive"))
      (node (ref "U4") (pin "28") (pinfunction "AN13/RB13_28") (pintype "passive"))
    )
    (net (code "54") (name "/LightR_OUT") (class "Default")
      (node (ref "D8") (pin "1") (pinfunction "A_1") (pintype "passive"))
      (node (ref "J5") (pin "8") (pinfunction "8_8") (pintype "passive"))
      (node (ref "Q5") (pin "1") (pinfunction "D_1") (pintype "passive"))
    )
    (net (code "55") (name "/MCLR") (class "Default")
      (node (ref "J3") (pin "1") (pinfunction "1_1") (pintype "passive"))
      (node (ref "R44") (pin "1") (pinfunction "1_1") (pintype "passive"))
      (node (ref "U4") (pin "7") (pinfunction "~{MCLR}_7") (pintype "passive"))
    )
    (net (code "56") (name "/PGC") (class "Default")
      (node (ref "J3") (pin "5") (pinfunction "5_5") (pintype "passive"))
      (node (ref "U4") (pin "17") (pinfunction "PGC/EMUC/AN6/OCFA/RB6_17") (pintype "passive"))
    )
    (net (code "57") (name "/PGD") (class "Default")
      (node (ref "J3") (pin "4") (pinfunction "4_4") (pintype "passive"))
      (node (ref "U4") (pin "18") (pinfunction "PGD/EMUD/AN7/RB7_18") (pintype "passive"))
    )
    (net (code "58") (name "/RESET") (class "Default")
      (node (ref "C23") (pin "2") (pinfunction "2_2") (pintype "passive"))
      (node (ref "D13") (pin "1") (pinfunction "A_1") (pintype "passive"))
      (node (ref "R42") (pin "2") (pinfunction "2_2") (pintype "passive"))
      (node (ref "R44") (pin "2") (pinfunction "2_2") (pintype "passive"))
      (node (ref "U5") (pin "1") (pinfunction "~{RST}_1") (pintype "passive"))
    )
    (net (code "59") (name "/RX") (class "Default")
      (node (ref "J2") (pin "10") (pinfunction "10_10") (pintype "passive"))
      (node (ref "U4") (pin "34") (pinfunction "U1RX/SDI1/RF2_34") (pintype "passive"))
    )
    (net (code "60") (name "/TX") (class "Default")
      (node (ref "J2") (pin "8") (pinfunction "8_8") (pintype "passive"))
      (node (ref "U4") (pin "33") (pinfunction "EMUD3/U1TX/SDO1/RF3_33") (pintype "passive"))
    )
    (net (code "61") (name "/WDI") (class "Default")
      (node (ref "R33") (pin "1") (pinfunction "1_1") (pintype "passive"))
      (node (ref "U5") (pin "4") (pinfunction "WDI_4") (pintype "passive"))
    )
    (net (code "62") (name "GND") (class "Default")
      (node (ref "C1") (pin "2") (pinfunction "2_2") (pintype "passive"))
      (node (ref "C10") (pin "2") (pinfunction "2_2") (pintype "passive"))
      (node (ref "C11") (pin "2") (pinfunction "2_2") (pintype "passive"))
      (node (ref "C12") (pin "2") (pinfunction "2_2") (pintype "passive"))
      (node (ref "C13") (pin "2") (pinfunction "2_2") (pintype "passive"))
      (node (ref "C14") (pin "2") (pinfunction "2_2") (pintype "passive"))
      (node (ref "C15") (pin "2") (pinfunction "2_2") (pintype "passive"))
      (node (ref "C16") (pin "2") (pinfunction "2_2") (pintype "passive"))
      (node (ref "C17") (pin "2") (pinfunction "2_2") (pintype "passive"))
      (node (ref "C18") (pin "2") (pinfunction "2_2") (pintype "passive"))
      (node (ref "C19") (pin "2") (pinfunction "2_2") (pintype "passive"))
      (node (ref "C2") (pin "1") (pinfunction "1_1") (pintype "passive"))
      (node (ref "C20") (pin "2") (pinfunction "2_2") (pintype "passive"))
      (node (ref "C21") (pin "2") (pinfunction "2_2") (pintype "passive"))
      (node (ref "C22") (pin "2") (pinfunction "2_2") (pintype "passive"))
      (node (ref "C23") (pin "1") (pinfunction "1_1") (pintype "passive"))
      (node (ref "C24") (pin "1") (pinfunction "1_1") (pintype "passive"))
      (node (ref "C3") (pin "2") (pinfunction "2_2") (pintype "passive"))
      (node (ref "C4") (pin "2") (pinfunction "2_2") (pintype "passive"))
      (node (ref "C5") (pin "2") (pinfunction "2_2") (pintype "passive"))
      (node (ref "C6") (pin "2") (pinfunction "2_2") (pintype "passive"))
      (node (ref "C7") (pin "1") (pinfunction "1_1") (pintype "passive"))
      (node (ref "C8") (pin "2") (pinfunction "2_2") (pintype "passive"))
      (node (ref "C9") (pin "1") (pinfunction "1_1") (pintype "passive"))
      (node (ref "D10") (pin "1") (pinfunction "A_1") (pintype "passive"))
      (node (ref "D11") (pin "1") (pinfunction "A_1") (pintype "passive"))
      (node (ref "D12") (pin "1") (pinfunction "A_1") (pintype "passive"))
      (node (ref "D2") (pin "1") (pinfunction "A_1") (pintype "passive"))
      (node (ref "D4") (pin "1") (pinfunction "A_1") (pintype "passive"))
      (node (ref "D6") (pin "1") (pinfunction "A_1") (pintype "passive"))
      (node (ref "D7") (pin "1") (pinfunction "A_1") (pintype "passive"))
      (node (ref "D9") (pin "1") (pinfunction "A_1") (pintype "passive"))
      (node (ref "J1") (pin "14") (pinfunction "14_14") (pintype "passive"))
      (node (ref "J2") (pin "12") (pinfunction "12_12") (pintype "passive"))
      (node (ref "J2") (pin "14") (pinfunction "14_14") (pintype "passive"))
      (node (ref "J3") (pin "3") (pinfunction "3_3") (pintype "passive"))
      (node (ref "J4") (pin "1") (pinfunction "1_1") (pintype "passive"))
      (node (ref "J5") (pin "1") (pinfunction "1_1") (pintype "passive"))
      (node (ref "LED4") (pin "2") (pinfunction "K_2") (pintype "passive"))
      (node (ref "Q1") (pin "2") (pinfunction "S_2") (pintype "passive"))
      (node (ref "Q2") (pin "2") (pinfunction "S_2") (pintype "passive"))
      (node (ref "Q3") (pin "2") (pinfunction "S_2") (pintype "passive"))
      (node (ref "Q4") (pin "2") (pinfunction "S_2") (pintype "passive"))
      (node (ref "Q5") (pin "2") (pinfunction "S_2") (pintype "passive"))
      (node (ref "Q6") (pin "2") (pinfunction "S_2") (pintype "passive"))
      (node (ref "Q7") (pin "2") (pinfunction "S_2") (pintype "passive"))
      (node (ref "R1") (pin "1") (pinfunction "1_1") (pintype "passive"))
      (node (ref "R11") (pin "1") (pinfunction "1_1") (pintype "passive"))
      (node (ref "R13") (pin "1") (pinfunction "1_1") (pintype "passive"))
      (node (ref "R14") (pin "2") (pinfunction "2_2") (pintype "passive"))
      (node (ref "R15") (pin "2") (pinfunction "2_2") (pintype "passive"))
      (node (ref "R18") (pin "2") (pinfunction "2_2") (pintype "passive"))
      (node (ref "R2") (pin "2") (pinfunction "2_2") (pintype "passive"))
      (node (ref "R24") (pin "2") (pinfunction "2_2") (pintype "passive"))
      (node (ref "R28") (pin "2") (pinfunction "2_2") (pintype "passive"))
      (node (ref "R34") (pin "2") (pinfunction "2_2") (pintype "passive"))
      (node (ref "R35") (pin "2") (pinfunction "2_2") (pintype "passive"))
      (node (ref "R45") (pin "2") (pinfunction "2_2") (pintype "passive"))
      (node (ref "R46") (pin "2") (pinfunction "2_2") (pintype "passive"))
      (node (ref "R6") (pin "2") (pinfunction "2_2") (pintype "passive"))
      (node (ref "S1") (pin "1") (pintype "passive"))
      (node (ref "U1") (pin "2") (pinfunction "GND_2") (pintype "power_in"))
      (node (ref "U2") (pin "4") (pinfunction "GND_4") (pintype "power_in"))
      (node (ref "U3") (pin "2") (pinfunction "GND_2") (pintype "power_in"))
      (node (ref "U4") (pin "20") (pinfunction "AVSS_20") (pintype "passive"))
      (node (ref "U4") (pin "25") (pinfunction "VSS_25") (pintype "passive"))
      (node (ref "U4") (pin "41") (pinfunction "VSS_41") (pintype "passive"))
      (node (ref "U4") (pin "56") (pinfunction "VSS_56") (pintype "passive"))
      (node (ref "U4") (pin "9") (pinfunction "VSS_9") (pintype "passive"))
      (node (ref "U5") (pin "2") (pinfunction "Vss_2") (pintype "passive"))
    )
    (net (code "63") (name "Net-(C2-Pad2)") (class "Default")
      (node (ref "C2") (pin "2") (pinfunction "2_2") (pintype "passive"))
      (node (ref "R3") (pin "2") (pinfunction "2_2") (pintype "passive"))
      (node (ref "R8") (pin "2") (pinfunction "2_2") (pintype "passive"))
      (node (ref "R9") (pin "2") (pinfunction "2_2") (pintype "passive"))
    )
    (net (code "64") (name "Net-(C9-Pad2)") (class "Default")
      (node (ref "C9") (pin "2") (pinfunction "2_2") (pintype "passive"))
      (node (ref "R16") (pin "2") (pinfunction "2_2") (pintype "passive"))
      (node (ref "R19") (pin "2") (pinfunction "2_2") (pintype "passive"))
      (node (ref "R20") (pin "2") (pinfunction "2_2") (pintype "passive"))
    )
    (net (code "65") (name "Net-(D2-K)") (class "Default")
      (node (ref "D2") (pin "2") (pinfunction "K_2") (pintype "passive"))
      (node (ref "L1") (pin "1") (pinfunction "1_1") (pintype "passive"))
      (node (ref "U2") (pin "2") (pinfunction "SWE_2") (pintype "open_emitter"))
    )
    (net (code "66") (name "Net-(D3-K)") (class "Default")
      (node (ref "D3") (pin "2") (pinfunction "K_2") (pintype "passive"))
      (node (ref "R21") (pin "2") (pinfunction "2_2") (pintype "passive"))
    )
    (net (code "67") (name "Net-(D5-K)") (class "Default")
      (node (ref "D5") (pin "2") (pinfunction "K_2") (pintype "passive"))
      (node (ref "R25") (pin "2") (pinfunction "2_2") (pintype "passive"))
    )
    (net (code "68") (name "Net-(D8-K)") (class "Default")
      (node (ref "D8") (pin "2") (pinfunction "K_2") (pintype "passive"))
      (node (ref "R29") (pin "2") (pinfunction "2_2") (pintype "passive"))
    )
    (net (code "69") (name "Net-(D14-A)") (class "Default")
      (node (ref "C24") (pin "2") (pinfunction "2_2") (pintype "passive"))
      (node (ref "D14") (pin "1") (pinfunction "A_1") (pintype "passive"))
      (node (ref "R43") (pin "1") (pinfunction "1_1") (pintype "passive"))
      (node (ref "S1") (pin "2") (pintype "passive"))
      (node (ref "U5") (pin "3") (pinfunction "~{MR}_3") (pintype "passive"))
    )
    (net (code "70") (name "Net-(LED1-K)") (class "Default")
      (node (ref "LED1") (pin "2") (pinfunction "K_2") (pintype "passive"))
      (node (ref "R5") (pin "1") (pinfunction "1_1") (pintype "passive"))
    )
    (net (code "71") (name "Net-(LED2-K)") (class "Default")
      (node (ref "LED2") (pin "2") (pinfunction "K_2") (pintype "passive"))
      (node (ref "R15") (pin "1") (pinfunction "1_1") (pintype "passive"))
    )
    (net (code "72") (name "Net-(LED3-K)") (class "Default")
      (node (ref "LED3") (pin "2") (pinfunction "K_2") (pintype "passive"))
      (node (ref "R17") (pin "1") (pinfunction "1_1") (pintype "passive"))
    )
    (net (code "73") (name "Net-(LED4-A)") (class "Default")
      (node (ref "LED4") (pin "1") (pinfunction "A_1") (pintype "passive"))
      (node (ref "R12") (pin "2") (pinfunction "2_2") (pintype "passive"))
    )
    (net (code "74") (name "Net-(LED5-K)") (class "Default")
      (node (ref "LED5") (pin "2") (pinfunction "K_2") (pintype "passive"))
      (node (ref "R30") (pin "1") (pinfunction "1_1") (pintype "passive"))
    )
    (net (code "75") (name "Net-(Q1-G)") (class "Default")
      (node (ref "Q1") (pin "3") (pinfunction "G_3") (pintype "passive"))
      (node (ref "R10") (pin "2") (pinfunction "2_2") (pintype "passive"))
    )
    (net (code "76") (name "Net-(Q4-D)") (class "Default")
      (node (ref "Q4") (pin "1") (pinfunction "D_1") (pintype "passive"))
      (node (ref "R21") (pin "1") (pinfunction "1_1") (pintype "passive"))
      (node (ref "R25") (pin "1") (pinfunction "1_1") (pintype "passive"))
      (node (ref "R29") (pin "1") (pinfunction "1_1") (pintype "passive"))
    )
    (net (code "77") (name "Net-(U1-RS)") (class "Default")
      (node (ref "R6") (pin "1") (pinfunction "1_1") (pintype "passive"))
      (node (ref "U1") (pin "8") (pinfunction "RS_8") (pintype "passive"))
    )
    (net (code "78") (name "Net-(U1-VREF)") (class "Default")
      (node (ref "R3") (pin "1") (pinfunction "1_1") (pintype "passive"))
      (node (ref "U1") (pin "5") (pinfunction "VREF_5") (pintype "output"))
    )
    (net (code "79") (name "Net-(U2--VIN)") (class "Default")
      (node (ref "R11") (pin "2") (pinfunction "2_2") (pintype "passive"))
      (node (ref "R7") (pin "2") (pinfunction "2_2") (pintype "passive"))
      (node (ref "U2") (pin "5") (pinfunction "-VIN_5") (pintype "input"))
    )
    (net (code "80") (name "Net-(U2-DRVC)") (class "Default")
      (node (ref "R4") (pin "1") (pinfunction "1_1") (pintype "passive"))
      (node (ref "U2") (pin "1") (pinfunction "SWC_1") (pintype "open_collector"))
      (node (ref "U2") (pin "7") (pinfunction "IPK_7") (pintype "passive"))
      (node (ref "U2") (pin "8") (pinfunction "DRVC_8") (pintype "open_collector"))
    )
    (net (code "81") (name "Net-(U2-TCAP)") (class "Default")
      (node (ref "C7") (pin "2") (pinfunction "2_2") (pintype "passive"))
      (node (ref "U2") (pin "3") (pinfunction "TCAP_3") (pintype "passive"))
    )
    (net (code "82") (name "Net-(U3-RS)") (class "Default")
      (node (ref "R18") (pin "1") (pinfunction "1_1") (pintype "passive"))
      (node (ref "U3") (pin "8") (pinfunction "RS_8") (pintype "passive"))
    )
    (net (code "83") (name "Net-(U3-VREF)") (class "Default")
      (node (ref "R16") (pin "1") (pinfunction "1_1") (pintype "passive"))
      (node (ref "U3") (pin "5") (pinfunction "VREF_5") (pintype "output"))
    )
    (net (code "84") (name "Net-(U4-OSC1{slash}CLKI)") (class "Default")
      (node (ref "C17") (pin "1") (pinfunction "1_1") (pintype "passive"))
      (node (ref "U4") (pin "39") (pinfunction "OSC1/CLKI_39") (pintype "passive"))
      (node (ref "Y1") (pin "2") (pinfunction "OSC2_2") (pintype "passive"))
    )
    (net (code "85") (name "Net-(U4-OSC2{slash}CLKO{slash}RC15)") (class "Default")
      (node (ref "C18") (pin "1") (pinfunction "1_1") (pintype "passive"))
      (node (ref "U4") (pin "40") (pinfunction "OSC2/CLKO/RC15_40") (pintype "passive"))
      (node (ref "Y1") (pin "1") (pinfunction "OSC1_1") (pintype "passive"))
    )
    (net (code "86") (name "Net-(U4-SCL{slash}RG2)") (class "Default")
      (node (ref "R30") (pin "2") (pinfunction "2_2") (pintype "passive"))
      (node (ref "U4") (pin "37") (pinfunction "SCL/RG2_37") (pintype "passive"))
    )
    (net (code "87") (name "Net-(U4-~{SS2}{slash}CN11{slash}RG9)") (class "Default")
      (node (ref "R33") (pin "2") (pinfunction "2_2") (pintype "passive"))
      (node (ref "U4") (pin "8") (pinfunction "~{SS2}/CN11/RG9_8") (pintype "passive"))
    )
    (net (code "88") (name "unconnected-(U4-COFS{slash}RG15-Pad1)") (class "Default")
      (node (ref "U4") (pin "1") (pinfunction "COFS/RG15_1") (pintype "passive"))
    )
    (net (code "89") (name "unconnected-(U4-CSCK{slash}RG14-Pad62)") (class "Default")
      (node (ref "U4") (pin "62") (pinfunction "CSCK/RG14_62") (pintype "passive"))
    )
    (net (code "90") (name "unconnected-(U4-CSDI{slash}RG12-Pad63)") (class "Default")
      (node (ref "U4") (pin "63") (pinfunction "CSDI/RG12_63") (pintype "passive"))
    )
    (net (code "91") (name "unconnected-(U4-CSDO{slash}RG13-Pad64)") (class "Default")
      (node (ref "U4") (pin "64") (pinfunction "CSDO/RG13_64") (pintype "passive"))
    )
    (net (code "92") (name "unconnected-(U4-EMUC3{slash}SCK1{slash}INT0{slash}RF6-Pad35)") (class "Default")
      (node (ref "U4") (pin "35") (pinfunction "EMUC3/SCK1/INT0/RF6_35") (pintype "passive"))
    )
    (net (code "93") (name "unconnected-(U4-SCK2{slash}CN8{slash}RG6-Pad4)") (class "Default")
      (node (ref "U4") (pin "4") (pinfunction "SCK2/CN8/RG6_4") (pintype "passive"))
    )
    (net (code "94") (name "unconnected-(U4-SDA{slash}RG3-Pad36)") (class "Default")
      (node (ref "U4") (pin "36") (pinfunction "SDA/RG3_36") (pintype "passive"))
    )
    (net (code "95") (name "unconnected-(U4-SDI2{slash}CN9{slash}RG7-Pad5)") (class "Default")
      (node (ref "U4") (pin "5") (pinfunction "SDI2/CN9/RG7_5") (pintype "passive"))
    )
    (net (code "96") (name "unconnected-(U4-SDO2{slash}CN10{slash}RG8-Pad6)") (class "Default")
      (node (ref "U4") (pin "6") (pinfunction "SDO2/CN10/RG8_6") (pintype "passive"))
    )
    (net (code "97") (name "unconnected-(U4-T2CK{slash}RC1-Pad2)") (class "Default")
      (node (ref "U4") (pin "2") (pinfunction "T2CK/RC1_2") (pintype "passive"))
    )
    (net (code "98") (name "unconnected-(U4-T3CK{slash}RC2-Pad3)") (class "Default")
      (node (ref "U4") (pin "3") (pinfunction "T3CK/RC2_3") (pintype "passive"))
    )
  )
)
